# Block.net
KiCad netlist of a schematic drawn in Altium Designer
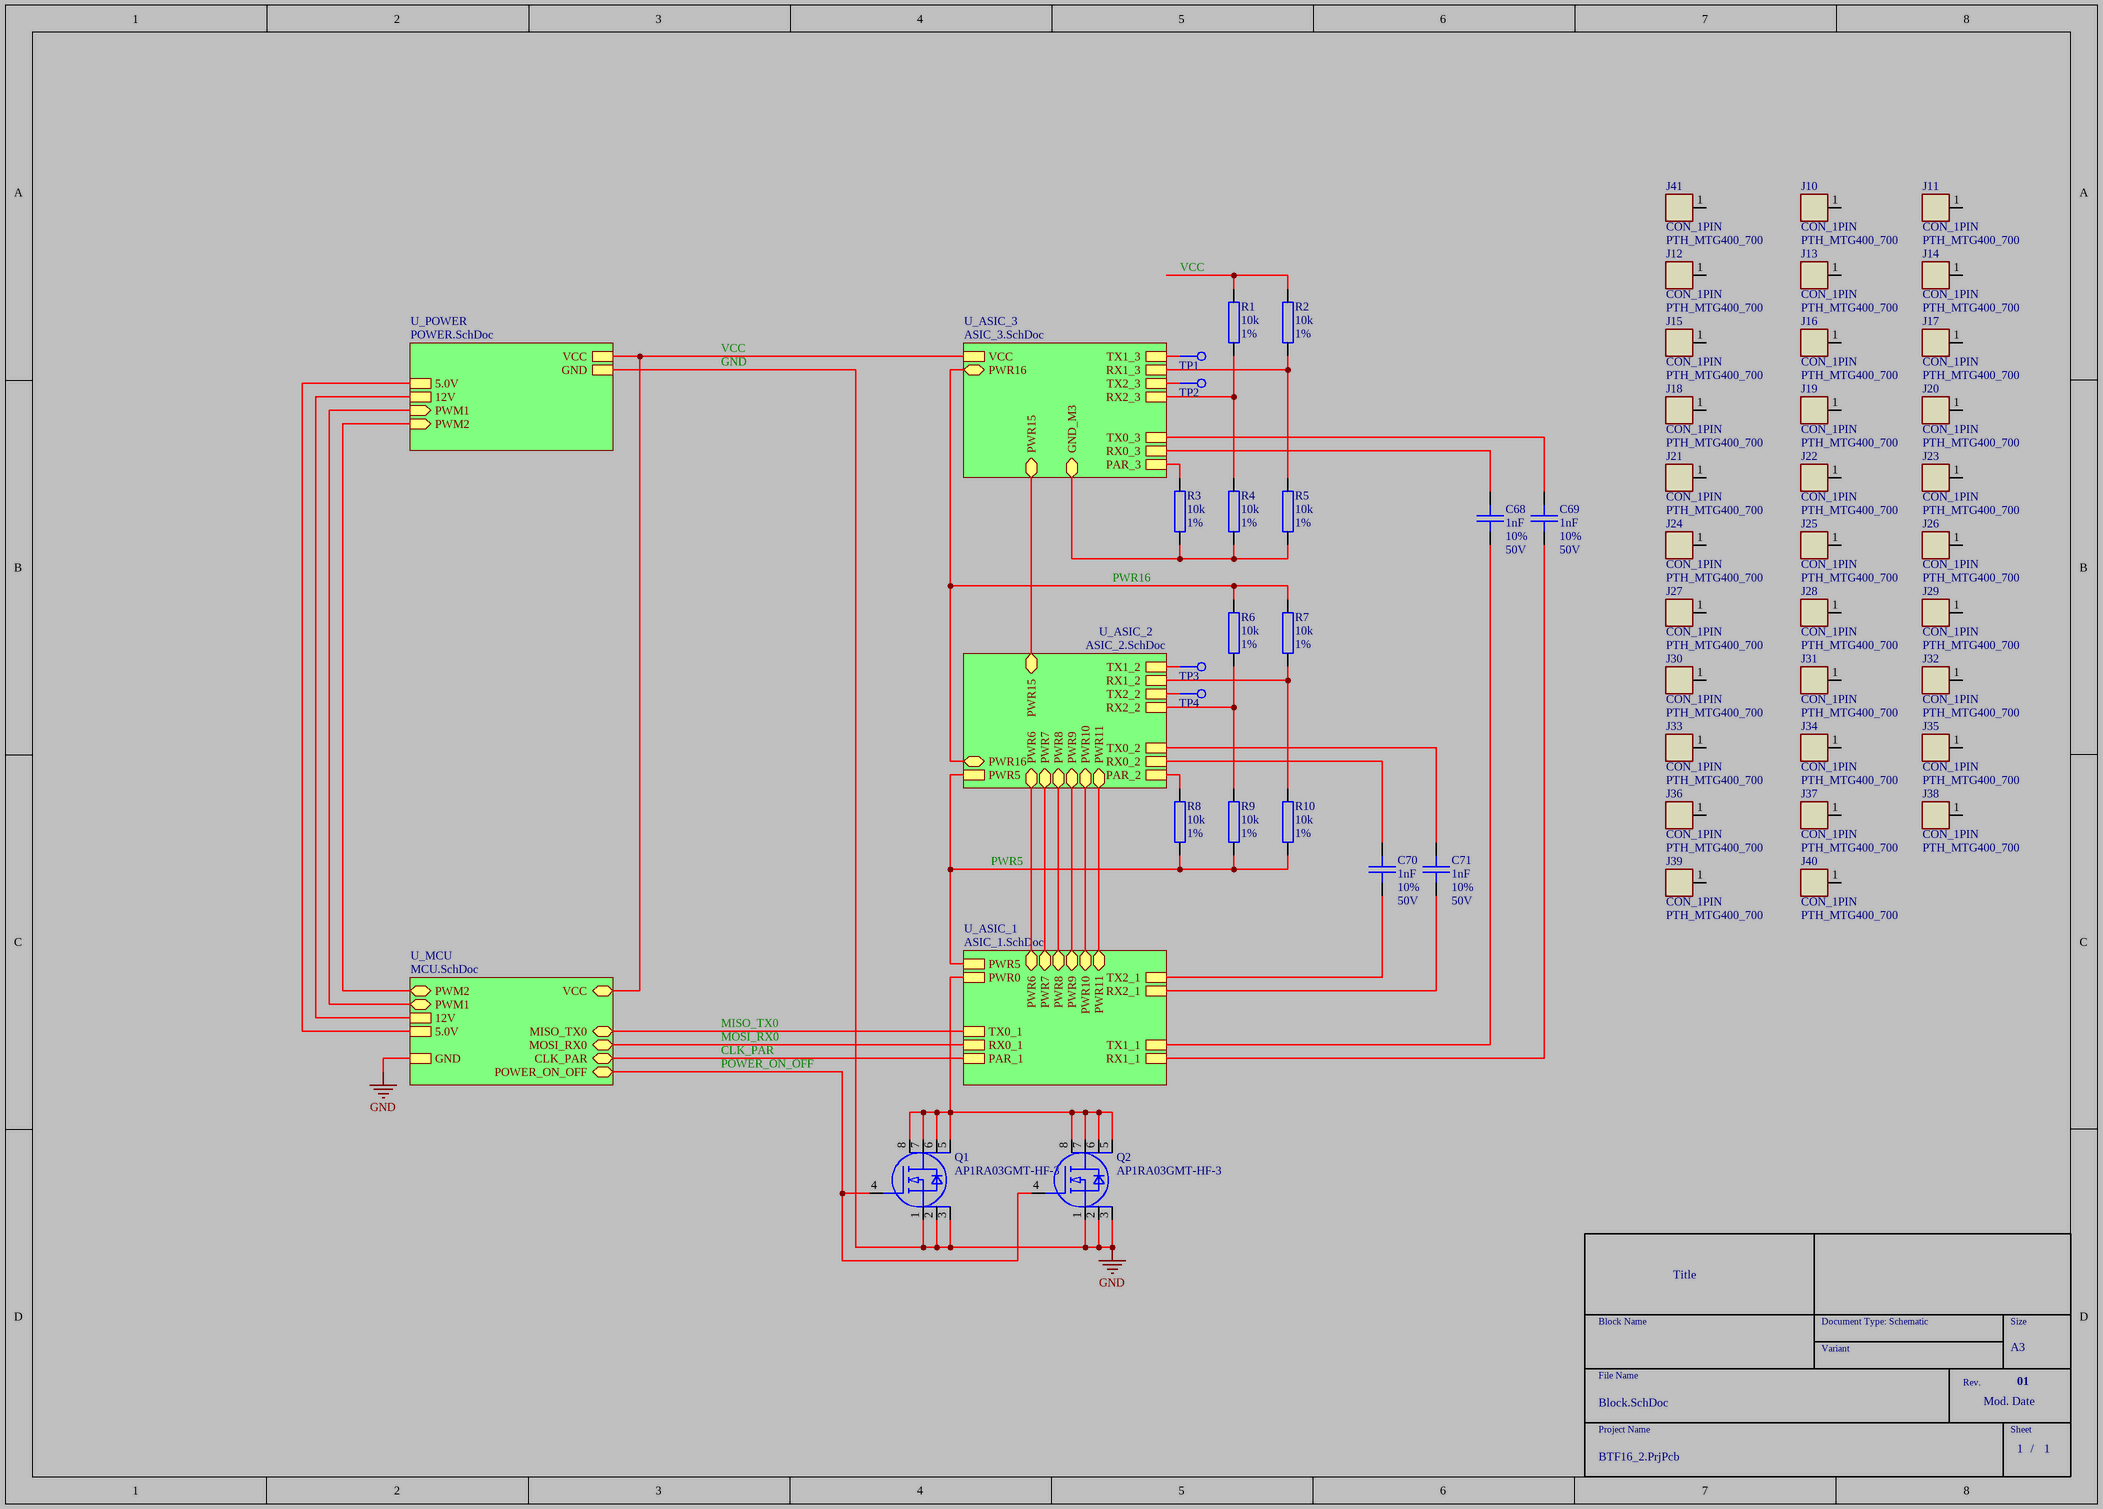
[diagram p0: Block.SchDoc]

(export (version "E")
  (design (tool "Eeschema 10.0.6"))
  (components
    (comp (ref "C68")
      (value "C")
      (footprint "SMD_0402_CAPC1005X55N")
      (fields
        (field (name "DB_PART_NUMBER") "CAP000020674")
        (field (name "DB_VALUE") "1nF")
        (field (name "DB_TOLERANCE") "10%")
        (field (name "DB_VOLTAGE") "50V")
        (field (name "DB_MANUFACTURER_PART") "KEMET    C0402F102K5RAC")
      )
      (libsource (lib "Database_Libs1") (part "C"))
    )
    (comp (ref "C69")
      (value "C")
      (footprint "SMD_0402_CAPC1005X55N")
      (fields
        (field (name "DB_PART_NUMBER") "CAP000020674")
        (field (name "DB_VALUE") "1nF")
        (field (name "DB_TOLERANCE") "10%")
        (field (name "DB_VOLTAGE") "50V")
        (field (name "DB_MANUFACTURER_PART") "KEMET    C0402F102K5RAC")
      )
      (libsource (lib "Database_Libs1") (part "C"))
    )
    (comp (ref "C70")
      (value "C")
      (footprint "SMD_0402_CAPC1005X55N")
      (fields
        (field (name "DB_PART_NUMBER") "CAP000020674")
        (field (name "DB_VALUE") "1nF")
        (field (name "DB_TOLERANCE") "10%")
        (field (name "DB_VOLTAGE") "50V")
        (field (name "DB_MANUFACTURER_PART") "KEMET    C0402F102K5RAC")
      )
      (libsource (lib "Database_Libs1") (part "C"))
    )
    (comp (ref "C71")
      (value "C")
      (footprint "SMD_0402_CAPC1005X55N")
      (fields
        (field (name "DB_PART_NUMBER") "CAP000020674")
        (field (name "DB_VALUE") "1nF")
        (field (name "DB_TOLERANCE") "10%")
        (field (name "DB_VOLTAGE") "50V")
        (field (name "DB_MANUFACTURER_PART") "KEMET    C0402F102K5RAC")
      )
      (libsource (lib "Database_Libs1") (part "C"))
    )
    (comp (ref "J10")
      (value "CON_1PIN")
      (footprint "PTH_MTG400_700")
      (fields
        (field (name "DB_PART_NUMBER") "MTH000000030")
        (field (name "DB_VALUE") "PTH_MTG400_700")
        (field (name "DB_APPROVED_BY") "VSN")
      )
      (libsource (lib "Database_Libs1") (part "CON_1PIN"))
    )
    (comp (ref "J11")
      (value "CON_1PIN")
      (footprint "PTH_MTG400_700")
      (fields
        (field (name "DB_PART_NUMBER") "MTH000000030")
        (field (name "DB_VALUE") "PTH_MTG400_700")
        (field (name "DB_APPROVED_BY") "VSN")
      )
      (libsource (lib "Database_Libs1") (part "CON_1PIN"))
    )
    (comp (ref "J12")
      (value "CON_1PIN")
      (footprint "PTH_MTG400_700")
      (fields
        (field (name "DB_PART_NUMBER") "MTH000000030")
        (field (name "DB_VALUE") "PTH_MTG400_700")
        (field (name "DB_APPROVED_BY") "VSN")
      )
      (libsource (lib "Database_Libs1") (part "CON_1PIN"))
    )
    (comp (ref "J13")
      (value "CON_1PIN")
      (footprint "PTH_MTG400_700")
      (fields
        (field (name "DB_PART_NUMBER") "MTH000000030")
        (field (name "DB_VALUE") "PTH_MTG400_700")
        (field (name "DB_APPROVED_BY") "VSN")
      )
      (libsource (lib "Database_Libs1") (part "CON_1PIN"))
    )
    (comp (ref "J14")
      (value "CON_1PIN")
      (footprint "PTH_MTG400_700")
      (fields
        (field (name "DB_PART_NUMBER") "MTH000000030")
        (field (name "DB_VALUE") "PTH_MTG400_700")
        (field (name "DB_APPROVED_BY") "VSN")
      )
      (libsource (lib "Database_Libs1") (part "CON_1PIN"))
    )
    (comp (ref "J15")
      (value "CON_1PIN")
      (footprint "PTH_MTG400_700")
      (fields
        (field (name "DB_PART_NUMBER") "MTH000000030")
        (field (name "DB_VALUE") "PTH_MTG400_700")
        (field (name "DB_APPROVED_BY") "VSN")
      )
      (libsource (lib "Database_Libs1") (part "CON_1PIN"))
    )
    (comp (ref "J16")
      (value "CON_1PIN")
      (footprint "PTH_MTG400_700")
      (fields
        (field (name "DB_PART_NUMBER") "MTH000000030")
        (field (name "DB_VALUE") "PTH_MTG400_700")
        (field (name "DB_APPROVED_BY") "VSN")
      )
      (libsource (lib "Database_Libs1") (part "CON_1PIN"))
    )
    (comp (ref "J17")
      (value "CON_1PIN")
      (footprint "PTH_MTG400_700")
      (fields
        (field (name "DB_PART_NUMBER") "MTH000000030")
        (field (name "DB_VALUE") "PTH_MTG400_700")
        (field (name "DB_APPROVED_BY") "VSN")
      )
      (libsource (lib "Database_Libs1") (part "CON_1PIN"))
    )
    (comp (ref "J18")
      (value "CON_1PIN")
      (footprint "PTH_MTG400_700")
      (fields
        (field (name "DB_PART_NUMBER") "MTH000000030")
        (field (name "DB_VALUE") "PTH_MTG400_700")
        (field (name "DB_APPROVED_BY") "VSN")
      )
      (libsource (lib "Database_Libs1") (part "CON_1PIN"))
    )
    (comp (ref "J19")
      (value "CON_1PIN")
      (footprint "PTH_MTG400_700")
      (fields
        (field (name "DB_PART_NUMBER") "MTH000000030")
        (field (name "DB_VALUE") "PTH_MTG400_700")
        (field (name "DB_APPROVED_BY") "VSN")
      )
      (libsource (lib "Database_Libs1") (part "CON_1PIN"))
    )
    (comp (ref "J20")
      (value "CON_1PIN")
      (footprint "PTH_MTG400_700")
      (fields
        (field (name "DB_PART_NUMBER") "MTH000000030")
        (field (name "DB_VALUE") "PTH_MTG400_700")
        (field (name "DB_APPROVED_BY") "VSN")
      )
      (libsource (lib "Database_Libs1") (part "CON_1PIN"))
    )
    (comp (ref "J21")
      (value "CON_1PIN")
      (footprint "PTH_MTG400_700")
      (fields
        (field (name "DB_PART_NUMBER") "MTH000000030")
        (field (name "DB_VALUE") "PTH_MTG400_700")
        (field (name "DB_APPROVED_BY") "VSN")
      )
      (libsource (lib "Database_Libs1") (part "CON_1PIN"))
    )
    (comp (ref "J22")
      (value "CON_1PIN")
      (footprint "PTH_MTG400_700")
      (fields
        (field (name "DB_PART_NUMBER") "MTH000000030")
        (field (name "DB_VALUE") "PTH_MTG400_700")
        (field (name "DB_APPROVED_BY") "VSN")
      )
      (libsource (lib "Database_Libs1") (part "CON_1PIN"))
    )
    (comp (ref "J23")
      (value "CON_1PIN")
      (footprint "PTH_MTG400_700")
      (fields
        (field (name "DB_PART_NUMBER") "MTH000000030")
        (field (name "DB_VALUE") "PTH_MTG400_700")
        (field (name "DB_APPROVED_BY") "VSN")
      )
      (libsource (lib "Database_Libs1") (part "CON_1PIN"))
    )
    (comp (ref "J24")
      (value "CON_1PIN")
      (footprint "PTH_MTG400_700")
      (fields
        (field (name "DB_PART_NUMBER") "MTH000000030")
        (field (name "DB_VALUE") "PTH_MTG400_700")
        (field (name "DB_APPROVED_BY") "VSN")
      )
      (libsource (lib "Database_Libs1") (part "CON_1PIN"))
    )
    (comp (ref "J25")
      (value "CON_1PIN")
      (footprint "PTH_MTG400_700")
      (fields
        (field (name "DB_PART_NUMBER") "MTH000000030")
        (field (name "DB_VALUE") "PTH_MTG400_700")
        (field (name "DB_APPROVED_BY") "VSN")
      )
      (libsource (lib "Database_Libs1") (part "CON_1PIN"))
    )
    (comp (ref "J26")
      (value "CON_1PIN")
      (footprint "PTH_MTG400_700")
      (fields
        (field (name "DB_PART_NUMBER") "MTH000000030")
        (field (name "DB_VALUE") "PTH_MTG400_700")
        (field (name "DB_APPROVED_BY") "VSN")
      )
      (libsource (lib "Database_Libs1") (part "CON_1PIN"))
    )
    (comp (ref "J27")
      (value "CON_1PIN")
      (footprint "PTH_MTG400_700")
      (fields
        (field (name "DB_PART_NUMBER") "MTH000000030")
        (field (name "DB_VALUE") "PTH_MTG400_700")
        (field (name "DB_APPROVED_BY") "VSN")
      )
      (libsource (lib "Database_Libs1") (part "CON_1PIN"))
    )
    (comp (ref "J28")
      (value "CON_1PIN")
      (footprint "PTH_MTG400_700")
      (fields
        (field (name "DB_PART_NUMBER") "MTH000000030")
        (field (name "DB_VALUE") "PTH_MTG400_700")
        (field (name "DB_APPROVED_BY") "VSN")
      )
      (libsource (lib "Database_Libs1") (part "CON_1PIN"))
    )
    (comp (ref "J29")
      (value "CON_1PIN")
      (footprint "PTH_MTG400_700")
      (fields
        (field (name "DB_PART_NUMBER") "MTH000000030")
        (field (name "DB_VALUE") "PTH_MTG400_700")
        (field (name "DB_APPROVED_BY") "VSN")
      )
      (libsource (lib "Database_Libs1") (part "CON_1PIN"))
    )
    (comp (ref "J30")
      (value "CON_1PIN")
      (footprint "PTH_MTG400_700")
      (fields
        (field (name "DB_PART_NUMBER") "MTH000000030")
        (field (name "DB_VALUE") "PTH_MTG400_700")
        (field (name "DB_APPROVED_BY") "VSN")
      )
      (libsource (lib "Database_Libs1") (part "CON_1PIN"))
    )
    (comp (ref "J31")
      (value "CON_1PIN")
      (footprint "PTH_MTG400_700")
      (fields
        (field (name "DB_PART_NUMBER") "MTH000000030")
        (field (name "DB_VALUE") "PTH_MTG400_700")
        (field (name "DB_APPROVED_BY") "VSN")
      )
      (libsource (lib "Database_Libs1") (part "CON_1PIN"))
    )
    (comp (ref "J32")
      (value "CON_1PIN")
      (footprint "PTH_MTG400_700")
      (fields
        (field (name "DB_PART_NUMBER") "MTH000000030")
        (field (name "DB_VALUE") "PTH_MTG400_700")
        (field (name "DB_APPROVED_BY") "VSN")
      )
      (libsource (lib "Database_Libs1") (part "CON_1PIN"))
    )
    (comp (ref "J33")
      (value "CON_1PIN")
      (footprint "PTH_MTG400_700")
      (fields
        (field (name "DB_PART_NUMBER") "MTH000000030")
        (field (name "DB_VALUE") "PTH_MTG400_700")
        (field (name "DB_APPROVED_BY") "VSN")
      )
      (libsource (lib "Database_Libs1") (part "CON_1PIN"))
    )
    (comp (ref "J34")
      (value "CON_1PIN")
      (footprint "PTH_MTG400_700")
      (fields
        (field (name "DB_PART_NUMBER") "MTH000000030")
        (field (name "DB_VALUE") "PTH_MTG400_700")
        (field (name "DB_APPROVED_BY") "VSN")
      )
      (libsource (lib "Database_Libs1") (part "CON_1PIN"))
    )
    (comp (ref "J35")
      (value "CON_1PIN")
      (footprint "PTH_MTG400_700")
      (fields
        (field (name "DB_PART_NUMBER") "MTH000000030")
        (field (name "DB_VALUE") "PTH_MTG400_700")
        (field (name "DB_APPROVED_BY") "VSN")
      )
      (libsource (lib "Database_Libs1") (part "CON_1PIN"))
    )
    (comp (ref "J36")
      (value "CON_1PIN")
      (footprint "PTH_MTG400_700")
      (fields
        (field (name "DB_PART_NUMBER") "MTH000000030")
        (field (name "DB_VALUE") "PTH_MTG400_700")
        (field (name "DB_APPROVED_BY") "VSN")
      )
      (libsource (lib "Database_Libs1") (part "CON_1PIN"))
    )
    (comp (ref "J37")
      (value "CON_1PIN")
      (footprint "PTH_MTG400_700")
      (fields
        (field (name "DB_PART_NUMBER") "MTH000000030")
        (field (name "DB_VALUE") "PTH_MTG400_700")
        (field (name "DB_APPROVED_BY") "VSN")
      )
      (libsource (lib "Database_Libs1") (part "CON_1PIN"))
    )
    (comp (ref "J38")
      (value "CON_1PIN")
      (footprint "PTH_MTG400_700")
      (fields
        (field (name "DB_PART_NUMBER") "MTH000000030")
        (field (name "DB_VALUE") "PTH_MTG400_700")
        (field (name "DB_APPROVED_BY") "VSN")
      )
      (libsource (lib "Database_Libs1") (part "CON_1PIN"))
    )
    (comp (ref "J39")
      (value "CON_1PIN")
      (footprint "PTH_MTG400_700")
      (fields
        (field (name "DB_PART_NUMBER") "MTH000000030")
        (field (name "DB_VALUE") "PTH_MTG400_700")
        (field (name "DB_APPROVED_BY") "VSN")
      )
      (libsource (lib "Database_Libs1") (part "CON_1PIN"))
    )
    (comp (ref "J40")
      (value "CON_1PIN")
      (footprint "PTH_MTG400_700")
      (fields
        (field (name "DB_PART_NUMBER") "MTH000000030")
        (field (name "DB_VALUE") "PTH_MTG400_700")
        (field (name "DB_APPROVED_BY") "VSN")
      )
      (libsource (lib "Database_Libs1") (part "CON_1PIN"))
    )
    (comp (ref "J41")
      (value "CON_1PIN")
      (footprint "PTH_MTG400_700")
      (fields
        (field (name "DB_PART_NUMBER") "MTH000000030")
        (field (name "DB_VALUE") "PTH_MTG400_700")
        (field (name "DB_APPROVED_BY") "VSN")
      )
      (libsource (lib "Database_Libs1") (part "CON_1PIN"))
    )
    (comp (ref "Q1")
      (value "MOS_N_D1_S1S2S3G4D5D6D7D8")
      (footprint "SMD_SOIC127P600X110-9AN")
      (fields
        (field (name "DB_PART_NUMBER") "TRA000001604")
        (field (name "DB_VALUE") "AP1RA03GMT-HF-3")
        (field (name "DB_MANUFACTURER_PART") "ADVANCED POWER ELECTRONICS CORP      AP1RA03GMT-HF-3")
        (field (name "DB_APPROVED_BY") "VSN")
      )
      (libsource (lib "Database_Libs1") (part "MOS_N_D1_S1S2S3G4D5D6D7D8"))
    )
    (comp (ref "Q2")
      (value "MOS_N_D1_S1S2S3G4D5D6D7D8")
      (footprint "SMD_SOIC127P600X110-9AN")
      (fields
        (field (name "DB_PART_NUMBER") "TRA000001604")
        (field (name "DB_VALUE") "AP1RA03GMT-HF-3")
        (field (name "DB_MANUFACTURER_PART") "ADVANCED POWER ELECTRONICS CORP      AP1RA03GMT-HF-3")
        (field (name "DB_APPROVED_BY") "VSN")
      )
      (libsource (lib "Database_Libs1") (part "MOS_N_D1_S1S2S3G4D5D6D7D8"))
    )
    (comp (ref "R1")
      (value "R")
      (footprint "SMD_0402_RESC1005X37N")
      (fields
        (field (name "DB_PART_NUMBER") "RES000008887")
        (field (name "DB_VALUE") "10k")
        (field (name "DB_TOLERANCE") "1%")
        (field (name "DB_MANUFACTURER_PART") "VISHAY    CRCW040210K0FKED")
        (field (name "DB_APPROVED_BY") "VSN")
      )
      (libsource (lib "Database_Libs1") (part "R"))
    )
    (comp (ref "R2")
      (value "R")
      (footprint "SMD_0402_RESC1005X37N")
      (fields
        (field (name "DB_PART_NUMBER") "RES000008887")
        (field (name "DB_VALUE") "10k")
        (field (name "DB_TOLERANCE") "1%")
        (field (name "DB_MANUFACTURER_PART") "VISHAY    CRCW040210K0FKED")
        (field (name "DB_APPROVED_BY") "VSN")
      )
      (libsource (lib "Database_Libs1") (part "R"))
    )
    (comp (ref "R3")
      (value "R")
      (footprint "SMD_0402_RESC1005X37N")
      (fields
        (field (name "DB_PART_NUMBER") "RES000008887")
        (field (name "DB_VALUE") "10k")
        (field (name "DB_TOLERANCE") "1%")
        (field (name "DB_MANUFACTURER_PART") "VISHAY    CRCW040210K0FKED")
        (field (name "DB_APPROVED_BY") "VSN")
      )
      (libsource (lib "Database_Libs1") (part "R"))
    )
    (comp (ref "R4")
      (value "R")
      (footprint "SMD_0402_RESC1005X37N")
      (fields
        (field (name "DB_PART_NUMBER") "RES000008887")
        (field (name "DB_VALUE") "10k")
        (field (name "DB_TOLERANCE") "1%")
        (field (name "DB_MANUFACTURER_PART") "VISHAY    CRCW040210K0FKED")
        (field (name "DB_APPROVED_BY") "VSN")
      )
      (libsource (lib "Database_Libs1") (part "R"))
    )
    (comp (ref "R5")
      (value "R")
      (footprint "SMD_0402_RESC1005X37N")
      (fields
        (field (name "DB_PART_NUMBER") "RES000008887")
        (field (name "DB_VALUE") "10k")
        (field (name "DB_TOLERANCE") "1%")
        (field (name "DB_MANUFACTURER_PART") "VISHAY    CRCW040210K0FKED")
        (field (name "DB_APPROVED_BY") "VSN")
      )
      (libsource (lib "Database_Libs1") (part "R"))
    )
    (comp (ref "R6")
      (value "R")
      (footprint "SMD_0402_RESC1005X37N")
      (fields
        (field (name "DB_PART_NUMBER") "RES000008887")
        (field (name "DB_VALUE") "10k")
        (field (name "DB_TOLERANCE") "1%")
        (field (name "DB_MANUFACTURER_PART") "VISHAY    CRCW040210K0FKED")
        (field (name "DB_APPROVED_BY") "VSN")
      )
      (libsource (lib "Database_Libs1") (part "R"))
    )
    (comp (ref "R7")
      (value "R")
      (footprint "SMD_0402_RESC1005X37N")
      (fields
        (field (name "DB_PART_NUMBER") "RES000008887")
        (field (name "DB_VALUE") "10k")
        (field (name "DB_TOLERANCE") "1%")
        (field (name "DB_MANUFACTURER_PART") "VISHAY    CRCW040210K0FKED")
        (field (name "DB_APPROVED_BY") "VSN")
      )
      (libsource (lib "Database_Libs1") (part "R"))
    )
    (comp (ref "R8")
      (value "R")
      (footprint "SMD_0402_RESC1005X37N")
      (fields
        (field (name "DB_PART_NUMBER") "RES000008887")
        (field (name "DB_VALUE") "10k")
        (field (name "DB_TOLERANCE") "1%")
        (field (name "DB_MANUFACTURER_PART") "VISHAY    CRCW040210K0FKED")
        (field (name "DB_APPROVED_BY") "VSN")
      )
      (libsource (lib "Database_Libs1") (part "R"))
    )
    (comp (ref "R9")
      (value "R")
      (footprint "SMD_0402_RESC1005X37N")
      (fields
        (field (name "DB_PART_NUMBER") "RES000008887")
        (field (name "DB_VALUE") "10k")
        (field (name "DB_TOLERANCE") "1%")
        (field (name "DB_MANUFACTURER_PART") "VISHAY    CRCW040210K0FKED")
        (field (name "DB_APPROVED_BY") "VSN")
      )
      (libsource (lib "Database_Libs1") (part "R"))
    )
    (comp (ref "R10")
      (value "R")
      (footprint "SMD_0402_RESC1005X37N")
      (fields
        (field (name "DB_PART_NUMBER") "RES000008887")
        (field (name "DB_VALUE") "10k")
        (field (name "DB_TOLERANCE") "1%")
        (field (name "DB_MANUFACTURER_PART") "VISHAY    CRCW040210K0FKED")
        (field (name "DB_APPROVED_BY") "VSN")
      )
      (libsource (lib "Database_Libs1") (part "R"))
    )
    (comp (ref "TP1")
      (value "TEST_POINT_1")
      (footprint "SMD_TP_100-254")
      (fields (field (name "DB_PART_NUMBER") "TPO000000001"))
      (libsource (lib "Database_Libs1") (part "TEST_POINT_1"))
    )
    (comp (ref "TP2")
      (value "TEST_POINT_1")
      (footprint "SMD_TP_100-254")
      (fields (field (name "DB_PART_NUMBER") "TPO000000001"))
      (libsource (lib "Database_Libs1") (part "TEST_POINT_1"))
    )
    (comp (ref "TP3")
      (value "TEST_POINT_1")
      (footprint "SMD_TP_100-254")
      (fields (field (name "DB_PART_NUMBER") "TPO000000001"))
      (libsource (lib "Database_Libs1") (part "TEST_POINT_1"))
    )
    (comp (ref "TP4")
      (value "TEST_POINT_1")
      (footprint "SMD_TP_100-254")
      (fields (field (name "DB_PART_NUMBER") "TPO000000001"))
      (libsource (lib "Database_Libs1") (part "TEST_POINT_1"))
    )
  )
  (nets
    (net (code "4") (name "/GND_M3") (class "Default")
      (node (ref "R3") (pin "2") (pinfunction "2_2") (pintype "passive"))
      (node (ref "R4") (pin "2") (pinfunction "2_2") (pintype "passive"))
      (node (ref "R5") (pin "2") (pinfunction "2_2") (pintype "passive"))
    )
    (net (code "7") (name "/PAR_2") (class "Default")
      (node (ref "R8") (pin "1") (pinfunction "1_1") (pintype "passive"))
    )
    (net (code "8") (name "/PAR_3") (class "Default")
      (node (ref "R3") (pin "1") (pinfunction "1_1") (pintype "passive"))
    )
    (net (code "9") (name "/POWER_ON_OFF") (class "Default")
      (node (ref "Q1") (pin "4") (pinfunction "G_4") (pintype "passive"))
      (node (ref "Q2") (pin "4") (pinfunction "G_4") (pintype "passive"))
    )
    (net (code "12") (name "/PWR0") (class "Default")
      (node (ref "Q1") (pin "5") (pinfunction "D_5") (pintype "passive"))
      (node (ref "Q1") (pin "6") (pinfunction "D_6") (pintype "passive"))
      (node (ref "Q1") (pin "7") (pinfunction "D_7") (pintype "passive"))
      (node (ref "Q1") (pin "8") (pinfunction "D_8") (pintype "passive"))
      (node (ref "Q2") (pin "5") (pinfunction "D_5") (pintype "passive"))
      (node (ref "Q2") (pin "6") (pinfunction "D_6") (pintype "passive"))
      (node (ref "Q2") (pin "7") (pinfunction "D_7") (pintype "passive"))
      (node (ref "Q2") (pin "8") (pinfunction "D_8") (pintype "passive"))
    )
    (net (code "13") (name "/PWR5") (class "Default")
      (node (ref "R10") (pin "2") (pinfunction "2_2") (pintype "passive"))
      (node (ref "R8") (pin "2") (pinfunction "2_2") (pintype "passive"))
      (node (ref "R9") (pin "2") (pinfunction "2_2") (pintype "passive"))
    )
    (net (code "21") (name "/PWR16") (class "Default")
      (node (ref "R6") (pin "2") (pinfunction "2_2") (pintype "passive"))
      (node (ref "R7") (pin "2") (pinfunction "2_2") (pintype "passive"))
    )
    (net (code "22") (name "/RX0_2") (class "Default")
      (node (ref "C70") (pin "1") (pinfunction "1_1") (pintype "passive"))
    )
    (net (code "23") (name "/RX0_3") (class "Default")
      (node (ref "C68") (pin "1") (pinfunction "1_1") (pintype "passive"))
    )
    (net (code "24") (name "/RX1_1") (class "Default")
      (node (ref "C69") (pin "2") (pinfunction "2_2") (pintype "passive"))
    )
    (net (code "25") (name "/RX1_2") (class "Default")
      (node (ref "R10") (pin "1") (pinfunction "1_1") (pintype "passive"))
      (node (ref "R7") (pin "1") (pinfunction "1_1") (pintype "passive"))
    )
    (net (code "26") (name "/RX1_3") (class "Default")
      (node (ref "R2") (pin "1") (pinfunction "1_1") (pintype "passive"))
      (node (ref "R5") (pin "1") (pinfunction "1_1") (pintype "passive"))
    )
    (net (code "27") (name "/RX2_1") (class "Default")
      (node (ref "C71") (pin "2") (pinfunction "2_2") (pintype "passive"))
    )
    (net (code "28") (name "/RX2_2") (class "Default")
      (node (ref "R6") (pin "1") (pinfunction "1_1") (pintype "passive"))
      (node (ref "R9") (pin "1") (pinfunction "1_1") (pintype "passive"))
    )
    (net (code "29") (name "/RX2_3") (class "Default")
      (node (ref "R1") (pin "1") (pinfunction "1_1") (pintype "passive"))
      (node (ref "R4") (pin "1") (pinfunction "1_1") (pintype "passive"))
    )
    (net (code "30") (name "/TX0_2") (class "Default")
      (node (ref "C71") (pin "1") (pinfunction "1_1") (pintype "passive"))
    )
    (net (code "31") (name "/TX0_3") (class "Default")
      (node (ref "C69") (pin "1") (pinfunction "1_1") (pintype "passive"))
    )
    (net (code "32") (name "/TX1_1") (class "Default")
      (node (ref "C68") (pin "2") (pinfunction "2_2") (pintype "passive"))
    )
    (net (code "33") (name "/TX1_2") (class "Default")
      (node (ref "TP3") (pin "1") (pinfunction "1_1") (pintype "passive"))
    )
    (net (code "34") (name "/TX1_3") (class "Default")
      (node (ref "TP1") (pin "1") (pinfunction "1_1") (pintype "passive"))
    )
    (net (code "35") (name "/TX2_1") (class "Default")
      (node (ref "C70") (pin "2") (pinfunction "2_2") (pintype "passive"))
    )
    (net (code "36") (name "/TX2_2") (class "Default")
      (node (ref "TP4") (pin "1") (pinfunction "1_1") (pintype "passive"))
    )
    (net (code "37") (name "/TX2_3") (class "Default")
      (node (ref "TP2") (pin "1") (pinfunction "1_1") (pintype "passive"))
    )
    (net (code "38") (name "/VCC") (class "Default")
      (node (ref "R1") (pin "2") (pinfunction "2_2") (pintype "passive"))
      (node (ref "R2") (pin "2") (pinfunction "2_2") (pintype "passive"))
    )
    (net (code "39") (name "GND") (class "Default")
      (node (ref "Q1") (pin "1") (pinfunction "S_1") (pintype "passive"))
      (node (ref "Q1") (pin "2") (pinfunction "S_2") (pintype "passive"))
      (node (ref "Q1") (pin "3") (pinfunction "S_3") (pintype "passive"))
      (node (ref "Q2") (pin "1") (pinfunction "S_1") (pintype "passive"))
      (node (ref "Q2") (pin "2") (pinfunction "S_2") (pintype "passive"))
      (node (ref "Q2") (pin "3") (pinfunction "S_3") (pintype "passive"))
    )
    (net (code "40") (name "unconnected-(J10-Pad1)") (class "Default")
      (node (ref "J10") (pin "1") (pinfunction "1_1") (pintype "passive"))
    )
    (net (code "41") (name "unconnected-(J11-Pad1)") (class "Default")
      (node (ref "J11") (pin "1") (pinfunction "1_1") (pintype "passive"))
    )
    (net (code "42") (name "unconnected-(J12-Pad1)") (class "Default")
      (node (ref "J12") (pin "1") (pinfunction "1_1") (pintype "passive"))
    )
    (net (code "43") (name "unconnected-(J13-Pad1)") (class "Default")
      (node (ref "J13") (pin "1") (pinfunction "1_1") (pintype "passive"))
    )
    (net (code "44") (name "unconnected-(J14-Pad1)") (class "Default")
      (node (ref "J14") (pin "1") (pinfunction "1_1") (pintype "passive"))
    )
    (net (code "45") (name "unconnected-(J15-Pad1)") (class "Default")
      (node (ref "J15") (pin "1") (pinfunction "1_1") (pintype "passive"))
    )
    (net (code "46") (name "unconnected-(J16-Pad1)") (class "Default")
      (node (ref "J16") (pin "1") (pinfunction "1_1") (pintype "passive"))
    )
    (net (code "47") (name "unconnected-(J17-Pad1)") (class "Default")
      (node (ref "J17") (pin "1") (pinfunction "1_1") (pintype "passive"))
    )
    (net (code "48") (name "unconnected-(J18-Pad1)") (class "Default")
      (node (ref "J18") (pin "1") (pinfunction "1_1") (pintype "passive"))
    )
    (net (code "49") (name "unconnected-(J19-Pad1)") (class "Default")
      (node (ref "J19") (pin "1") (pinfunction "1_1") (pintype "passive"))
    )
    (net (code "50") (name "unconnected-(J20-Pad1)") (class "Default")
      (node (ref "J20") (pin "1") (pinfunction "1_1") (pintype "passive"))
    )
    (net (code "51") (name "unconnected-(J21-Pad1)") (class "Default")
      (node (ref "J21") (pin "1") (pinfunction "1_1") (pintype "passive"))
    )
    (net (code "52") (name "unconnected-(J22-Pad1)") (class "Default")
      (node (ref "J22") (pin "1") (pinfunction "1_1") (pintype "passive"))
    )
    (net (code "53") (name "unconnected-(J23-Pad1)") (class "Default")
      (node (ref "J23") (pin "1") (pinfunction "1_1") (pintype "passive"))
    )
    (net (code "54") (name "unconnected-(J24-Pad1)") (class "Default")
      (node (ref "J24") (pin "1") (pinfunction "1_1") (pintype "passive"))
    )
    (net (code "55") (name "unconnected-(J25-Pad1)") (class "Default")
      (node (ref "J25") (pin "1") (pinfunction "1_1") (pintype "passive"))
    )
    (net (code "56") (name "unconnected-(J26-Pad1)") (class "Default")
      (node (ref "J26") (pin "1") (pinfunction "1_1") (pintype "passive"))
    )
    (net (code "57") (name "unconnected-(J27-Pad1)") (class "Default")
      (node (ref "J27") (pin "1") (pinfunction "1_1") (pintype "passive"))
    )
    (net (code "58") (name "unconnected-(J28-Pad1)") (class "Default")
      (node (ref "J28") (pin "1") (pinfunction "1_1") (pintype "passive"))
    )
    (net (code "59") (name "unconnected-(J29-Pad1)") (class "Default")
      (node (ref "J29") (pin "1") (pinfunction "1_1") (pintype "passive"))
    )
    (net (code "60") (name "unconnected-(J30-Pad1)") (class "Default")
      (node (ref "J30") (pin "1") (pinfunction "1_1") (pintype "passive"))
    )
    (net (code "61") (name "unconnected-(J31-Pad1)") (class "Default")
      (node (ref "J31") (pin "1") (pinfunction "1_1") (pintype "passive"))
    )
    (net (code "62") (name "unconnected-(J32-Pad1)") (class "Default")
      (node (ref "J32") (pin "1") (pinfunction "1_1") (pintype "passive"))
    )
    (net (code "63") (name "unconnected-(J33-Pad1)") (class "Default")
      (node (ref "J33") (pin "1") (pinfunction "1_1") (pintype "passive"))
    )
    (net (code "64") (name "unconnected-(J34-Pad1)") (class "Default")
      (node (ref "J34") (pin "1") (pinfunction "1_1") (pintype "passive"))
    )
    (net (code "65") (name "unconnected-(J35-Pad1)") (class "Default")
      (node (ref "J35") (pin "1") (pinfunction "1_1") (pintype "passive"))
    )
    (net (code "66") (name "unconnected-(J36-Pad1)") (class "Default")
      (node (ref "J36") (pin "1") (pinfunction "1_1") (pintype "passive"))
    )
    (net (code "67") (name "unconnected-(J37-Pad1)") (class "Default")
      (node (ref "J37") (pin "1") (pinfunction "1_1") (pintype "passive"))
    )
    (net (code "68") (name "unconnected-(J38-Pad1)") (class "Default")
      (node (ref "J38") (pin "1") (pinfunction "1_1") (pintype "passive"))
    )
    (net (code "69") (name "unconnected-(J39-Pad1)") (class "Default")
      (node (ref "J39") (pin "1") (pinfunction "1_1") (pintype "passive"))
    )
    (net (code "70") (name "unconnected-(J40-Pad1)") (class "Default")
      (node (ref "J40") (pin "1") (pinfunction "1_1") (pintype "passive"))
    )
    (net (code "71") (name "unconnected-(J41-Pad1)") (class "Default")
      (node (ref "J41") (pin "1") (pinfunction "1_1") (pintype "passive"))
    )
  )
)
